# DDR3-RAM.net
KiCad netlist of a schematic drawn in Altium Designer
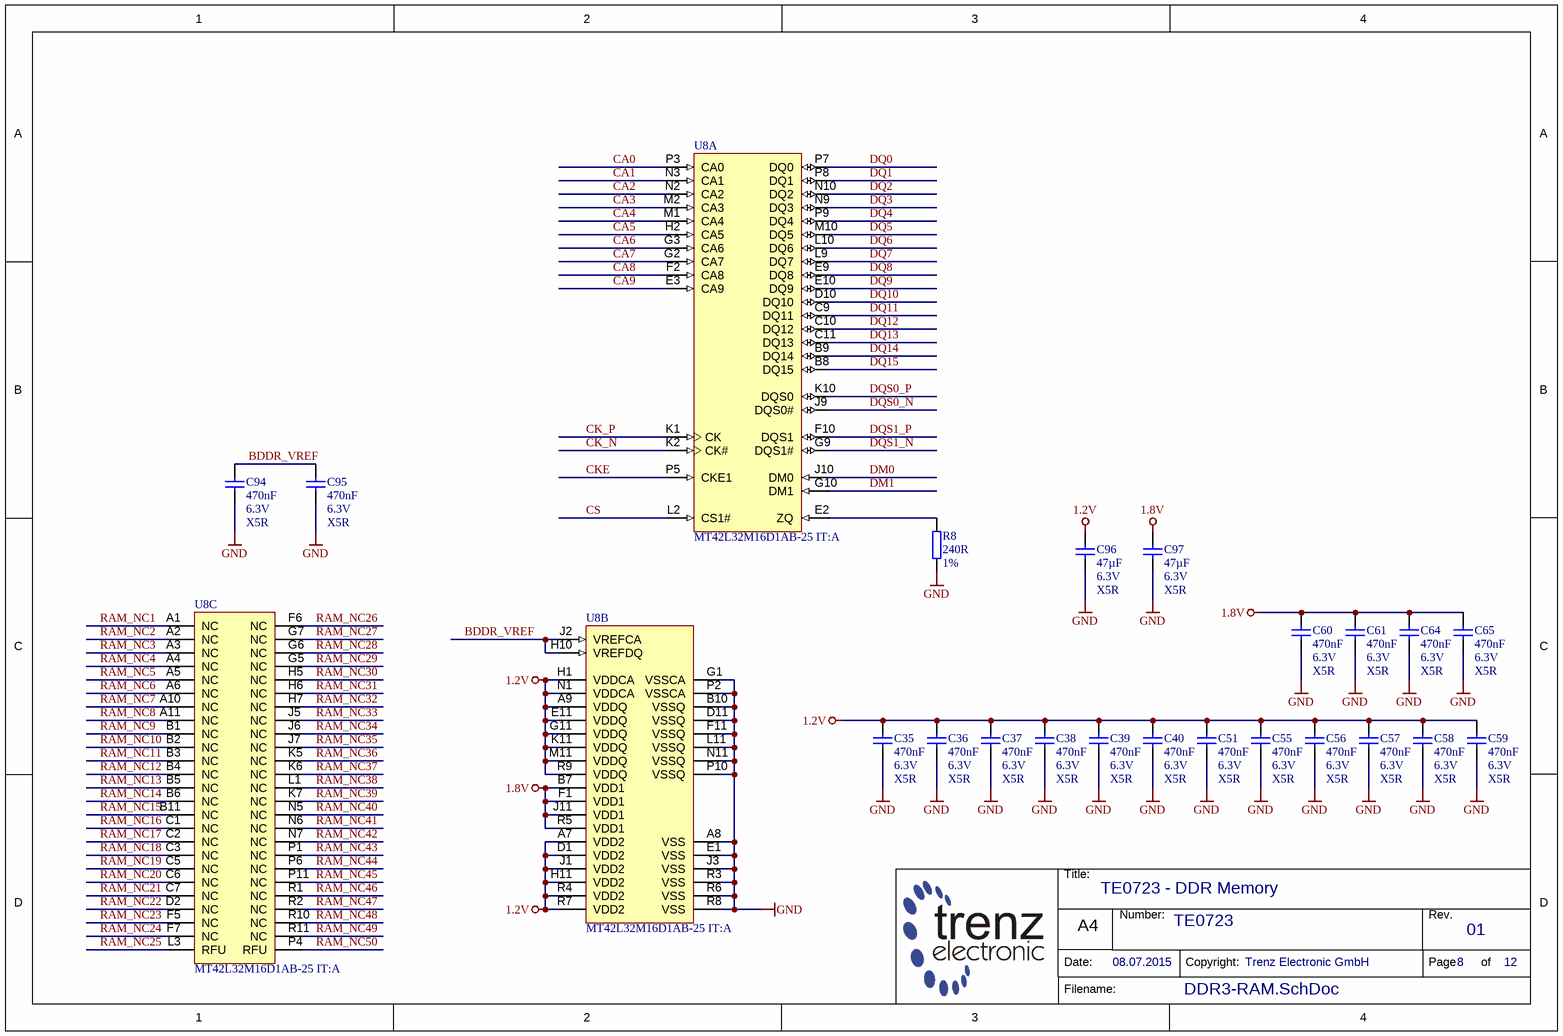
[diagram p0: DDR3-RAM.SchDoc]

(export (version "E")
  (design (tool "Eeschema 10.0.6"))
  (components
    (comp (ref "C35")
      (value "470nF")
      (footprint "CAPC0603X33N")
      (description "KON 470nF X5R 6.3V SMD 20%")
      (fields
        (field (name "VOLTAGE") "6.3V")
        (field (name "TECHNOLOGY") "X5R")
        (field (name "TOLERANCE") "20%")
      )
      (libsource (lib "TE") (part "CAP-NP"))
    )
    (comp (ref "C36")
      (value "470nF")
      (footprint "CAPC0603X33N")
      (description "KON 470nF X5R 6.3V SMD 20%")
      (fields
        (field (name "VOLTAGE") "6.3V")
        (field (name "TECHNOLOGY") "X5R")
        (field (name "TOLERANCE") "20%")
      )
      (libsource (lib "TE") (part "CAP-NP"))
    )
    (comp (ref "C37")
      (value "470nF")
      (footprint "CAPC0603X33N")
      (description "KON 470nF X5R 6.3V SMD 20%")
      (fields
        (field (name "VOLTAGE") "6.3V")
        (field (name "TECHNOLOGY") "X5R")
        (field (name "TOLERANCE") "20%")
      )
      (libsource (lib "TE") (part "CAP-NP"))
    )
    (comp (ref "C38")
      (value "470nF")
      (footprint "CAPC0603X33N")
      (description "KON 470nF X5R 6.3V SMD 20%")
      (fields
        (field (name "VOLTAGE") "6.3V")
        (field (name "TECHNOLOGY") "X5R")
        (field (name "TOLERANCE") "20%")
      )
      (libsource (lib "TE") (part "CAP-NP"))
    )
    (comp (ref "C39")
      (value "470nF")
      (footprint "CAPC0603X33N")
      (description "KON 470nF X5R 6.3V SMD 20%")
      (fields
        (field (name "VOLTAGE") "6.3V")
        (field (name "TECHNOLOGY") "X5R")
        (field (name "TOLERANCE") "20%")
      )
      (libsource (lib "TE") (part "CAP-NP"))
    )
    (comp (ref "C40")
      (value "470nF")
      (footprint "CAPC0603X33N")
      (description "KON 470nF X5R 6.3V SMD 20%")
      (fields
        (field (name "VOLTAGE") "6.3V")
        (field (name "TECHNOLOGY") "X5R")
        (field (name "TOLERANCE") "20%")
      )
      (libsource (lib "TE") (part "CAP-NP"))
    )
    (comp (ref "C51")
      (value "470nF")
      (footprint "CAPC0603X33N")
      (description "KON 470nF X5R 6.3V SMD 20%")
      (fields
        (field (name "VOLTAGE") "6.3V")
        (field (name "TECHNOLOGY") "X5R")
        (field (name "TOLERANCE") "20%")
      )
      (libsource (lib "TE") (part "CAP-NP"))
    )
    (comp (ref "C55")
      (value "470nF")
      (footprint "CAPC0603X33N")
      (description "KON 470nF X5R 6.3V SMD 20%")
      (fields
        (field (name "VOLTAGE") "6.3V")
        (field (name "TECHNOLOGY") "X5R")
        (field (name "TOLERANCE") "20%")
      )
      (libsource (lib "TE") (part "CAP-NP"))
    )
    (comp (ref "C56")
      (value "470nF")
      (footprint "CAPC0603X33N")
      (description "KON 470nF X5R 6.3V SMD 20%")
      (fields
        (field (name "VOLTAGE") "6.3V")
        (field (name "TECHNOLOGY") "X5R")
        (field (name "TOLERANCE") "20%")
      )
      (libsource (lib "TE") (part "CAP-NP"))
    )
    (comp (ref "C57")
      (value "470nF")
      (footprint "CAPC0603X33N")
      (description "KON 470nF X5R 6.3V SMD 20%")
      (fields
        (field (name "VOLTAGE") "6.3V")
        (field (name "TECHNOLOGY") "X5R")
        (field (name "TOLERANCE") "20%")
      )
      (libsource (lib "TE") (part "CAP-NP"))
    )
    (comp (ref "C58")
      (value "470nF")
      (footprint "CAPC0603X33N")
      (description "KON 470nF X5R 6.3V SMD 20%")
      (fields
        (field (name "VOLTAGE") "6.3V")
        (field (name "TECHNOLOGY") "X5R")
        (field (name "TOLERANCE") "20%")
      )
      (libsource (lib "TE") (part "CAP-NP"))
    )
    (comp (ref "C59")
      (value "470nF")
      (footprint "CAPC0603X33N")
      (description "KON 470nF X5R 6.3V SMD 20%")
      (fields
        (field (name "VOLTAGE") "6.3V")
        (field (name "TECHNOLOGY") "X5R")
        (field (name "TOLERANCE") "20%")
      )
      (libsource (lib "TE") (part "CAP-NP"))
    )
    (comp (ref "C60")
      (value "470nF")
      (footprint "CAPC0603X33N")
      (description "KON 470nF X5R 6.3V SMD 20%")
      (fields
        (field (name "VOLTAGE") "6.3V")
        (field (name "TECHNOLOGY") "X5R")
        (field (name "TOLERANCE") "20%")
      )
      (libsource (lib "TE") (part "CAP-NP"))
    )
    (comp (ref "C61")
      (value "470nF")
      (footprint "CAPC0603X33N")
      (description "KON 470nF X5R 6.3V SMD 20%")
      (fields
        (field (name "VOLTAGE") "6.3V")
        (field (name "TECHNOLOGY") "X5R")
        (field (name "TOLERANCE") "20%")
      )
      (libsource (lib "TE") (part "CAP-NP"))
    )
    (comp (ref "C64")
      (value "470nF")
      (footprint "CAPC0603X33N")
      (description "KON 470nF X5R 6.3V SMD 20%")
      (fields
        (field (name "VOLTAGE") "6.3V")
        (field (name "TECHNOLOGY") "X5R")
        (field (name "TOLERANCE") "20%")
      )
      (libsource (lib "TE") (part "CAP-NP"))
    )
    (comp (ref "C65")
      (value "470nF")
      (footprint "CAPC0603X33N")
      (description "KON 470nF X5R 6.3V SMD 20%")
      (fields
        (field (name "VOLTAGE") "6.3V")
        (field (name "TECHNOLOGY") "X5R")
        (field (name "TOLERANCE") "20%")
      )
      (libsource (lib "TE") (part "CAP-NP"))
    )
    (comp (ref "C94")
      (value "470nF")
      (footprint "CAPC0603X33N")
      (description "KON 470nF X5R 6.3V SMD 20%")
      (fields
        (field (name "VOLTAGE") "6.3V")
        (field (name "TECHNOLOGY") "X5R")
        (field (name "TOLERANCE") "20%")
      )
      (libsource (lib "TE") (part "CAP-NP"))
    )
    (comp (ref "C95")
      (value "470nF")
      (footprint "CAPC0603X33N")
      (description "KON 470nF X5R 6.3V SMD 20%")
      (fields
        (field (name "VOLTAGE") "6.3V")
        (field (name "TECHNOLOGY") "X5R")
        (field (name "TOLERANCE") "20%")
      )
      (libsource (lib "TE") (part "CAP-NP"))
    )
    (comp (ref "C96")
      (value "47µF")
      (footprint "CAPC2012X135N")
      (description "KON 47µF 6,3V  X5R SMD 20%")
      (fields
        (field (name "VOLTAGE") "6.3V")
        (field (name "TECHNOLOGY") "X5R")
        (field (name "TOLERANCE") "20%")
      )
      (libsource (lib "TE") (part "CAP-NP"))
    )
    (comp (ref "C97")
      (value "47µF")
      (footprint "CAPC2012X135N")
      (description "KON 47µF 6,3V  X5R SMD 20%")
      (fields
        (field (name "VOLTAGE") "6.3V")
        (field (name "TECHNOLOGY") "X5R")
        (field (name "TOLERANCE") "20%")
      )
      (libsource (lib "TE") (part "CAP-NP"))
    )
    (comp (ref "R8")
      (value "240R")
      (footprint "RESC1005X40N")
      (description "WID SMD 240R 1% 0,063W")
      (fields (field (name "TOLERANCE") "1%"))
      (libsource (lib "TE") (part "RES"))
    )
    (comp (ref "U8")
      (value "MT42L32M16D1AB-25 IT:A")
      (footprint "BGA121C50P15X11_800X650X80B32N")
      (libsource (lib "TE") (part "MT42L32M16D1AB"))
    )
  )
  (nets
    (net (code "1") (name "/BDDR_VREF") (class "Default")
      (node (ref "C94") (pin "1") (pinfunction "1_1") (pintype "passive"))
      (node (ref "C95") (pin "1") (pinfunction "1_1") (pintype "passive"))
      (node (ref "U8") (pin "H10") (pinfunction "VREFDQ_H10") (pintype "input"))
      (node (ref "U8") (pin "J2") (pinfunction "VREFCA_J2") (pintype "input"))
    )
    (net (code "2") (name "/CA0") (class "Default")
      (node (ref "U8") (pin "P3") (pinfunction "CA0_P3") (pintype "input"))
    )
    (net (code "3") (name "/CA1") (class "Default")
      (node (ref "U8") (pin "N3") (pinfunction "CA1_N3") (pintype "input"))
    )
    (net (code "4") (name "/CA2") (class "Default")
      (node (ref "U8") (pin "N2") (pinfunction "CA2_N2") (pintype "input"))
    )
    (net (code "5") (name "/CA3") (class "Default")
      (node (ref "U8") (pin "M2") (pinfunction "CA3_M2") (pintype "input"))
    )
    (net (code "6") (name "/CA4") (class "Default")
      (node (ref "U8") (pin "M1") (pinfunction "CA4_M1") (pintype "input"))
    )
    (net (code "7") (name "/CA5") (class "Default")
      (node (ref "U8") (pin "H2") (pinfunction "CA5_H2") (pintype "input"))
    )
    (net (code "8") (name "/CA6") (class "Default")
      (node (ref "U8") (pin "G3") (pinfunction "CA6_G3") (pintype "input"))
    )
    (net (code "9") (name "/CA7") (class "Default")
      (node (ref "U8") (pin "G2") (pinfunction "CA7_G2") (pintype "input"))
    )
    (net (code "10") (name "/CA8") (class "Default")
      (node (ref "U8") (pin "F2") (pinfunction "CA8_F2") (pintype "input"))
    )
    (net (code "11") (name "/CA9") (class "Default")
      (node (ref "U8") (pin "E3") (pinfunction "CA9_E3") (pintype "input"))
    )
    (net (code "12") (name "/CKE") (class "Default")
      (node (ref "U8") (pin "P5") (pinfunction "CKE1_P5") (pintype "input"))
    )
    (net (code "13") (name "/CK_N") (class "Default")
      (node (ref "U8") (pin "K2") (pinfunction "CK#_K2") (pintype "input"))
    )
    (net (code "14") (name "/CK_P") (class "Default")
      (node (ref "U8") (pin "K1") (pinfunction "CK_K1") (pintype "input"))
    )
    (net (code "15") (name "/CS") (class "Default")
      (node (ref "U8") (pin "L2") (pinfunction "CS1#_L2") (pintype "input"))
    )
    (net (code "16") (name "/DM0") (class "Default")
      (node (ref "U8") (pin "J10") (pinfunction "DM0_J10") (pintype "input"))
    )
    (net (code "17") (name "/DM1") (class "Default")
      (node (ref "U8") (pin "G10") (pinfunction "DM1_G10") (pintype "input"))
    )
    (net (code "18") (name "/DQ0") (class "Default")
      (node (ref "U8") (pin "P7") (pinfunction "DQ0_P7") (pintype "bidirectional"))
    )
    (net (code "19") (name "/DQ1") (class "Default")
      (node (ref "U8") (pin "P8") (pinfunction "DQ1_P8") (pintype "bidirectional"))
    )
    (net (code "20") (name "/DQ2") (class "Default")
      (node (ref "U8") (pin "N10") (pinfunction "DQ2_N10") (pintype "bidirectional"))
    )
    (net (code "21") (name "/DQ3") (class "Default")
      (node (ref "U8") (pin "N9") (pinfunction "DQ3_N9") (pintype "bidirectional"))
    )
    (net (code "22") (name "/DQ4") (class "Default")
      (node (ref "U8") (pin "P9") (pinfunction "DQ4_P9") (pintype "bidirectional"))
    )
    (net (code "23") (name "/DQ5") (class "Default")
      (node (ref "U8") (pin "M10") (pinfunction "DQ5_M10") (pintype "bidirectional"))
    )
    (net (code "24") (name "/DQ6") (class "Default")
      (node (ref "U8") (pin "L10") (pinfunction "DQ6_L10") (pintype "bidirectional"))
    )
    (net (code "25") (name "/DQ7") (class "Default")
      (node (ref "U8") (pin "L9") (pinfunction "DQ7_L9") (pintype "bidirectional"))
    )
    (net (code "26") (name "/DQ8") (class "Default")
      (node (ref "U8") (pin "E9") (pinfunction "DQ8_E9") (pintype "bidirectional"))
    )
    (net (code "27") (name "/DQ9") (class "Default")
      (node (ref "U8") (pin "E10") (pinfunction "DQ9_E10") (pintype "bidirectional"))
    )
    (net (code "28") (name "/DQ10") (class "Default")
      (node (ref "U8") (pin "D10") (pinfunction "DQ10_D10") (pintype "bidirectional"))
    )
    (net (code "29") (name "/DQ11") (class "Default")
      (node (ref "U8") (pin "C9") (pinfunction "DQ11_C9") (pintype "bidirectional"))
    )
    (net (code "30") (name "/DQ12") (class "Default")
      (node (ref "U8") (pin "C10") (pinfunction "DQ12_C10") (pintype "bidirectional"))
    )
    (net (code "31") (name "/DQ13") (class "Default")
      (node (ref "U8") (pin "C11") (pinfunction "DQ13_C11") (pintype "bidirectional"))
    )
    (net (code "32") (name "/DQ14") (class "Default")
      (node (ref "U8") (pin "B9") (pinfunction "DQ14_B9") (pintype "bidirectional"))
    )
    (net (code "33") (name "/DQ15") (class "Default")
      (node (ref "U8") (pin "B8") (pinfunction "DQ15_B8") (pintype "bidirectional"))
    )
    (net (code "34") (name "/DQS0_N") (class "Default")
      (node (ref "U8") (pin "J9") (pinfunction "DQS0#_J9") (pintype "bidirectional"))
    )
    (net (code "35") (name "/DQS0_P") (class "Default")
      (node (ref "U8") (pin "K10") (pinfunction "DQS0_K10") (pintype "bidirectional"))
    )
    (net (code "36") (name "/DQS1_N") (class "Default")
      (node (ref "U8") (pin "G9") (pinfunction "DQS1#_G9") (pintype "bidirectional"))
    )
    (net (code "37") (name "/DQS1_P") (class "Default")
      (node (ref "U8") (pin "F10") (pinfunction "DQS1_F10") (pintype "bidirectional"))
    )
    (net (code "38") (name "/RAM_NC1") (class "Default")
      (node (ref "U8") (pin "A1") (pinfunction "NC_A1") (pintype "passive"))
    )
    (net (code "39") (name "/RAM_NC2") (class "Default")
      (node (ref "U8") (pin "A2") (pinfunction "NC_A2") (pintype "passive"))
    )
    (net (code "40") (name "/RAM_NC3") (class "Default")
      (node (ref "U8") (pin "A3") (pinfunction "NC_A3") (pintype "passive"))
    )
    (net (code "41") (name "/RAM_NC4") (class "Default")
      (node (ref "U8") (pin "A4") (pinfunction "NC_A4") (pintype "passive"))
    )
    (net (code "42") (name "/RAM_NC5") (class "Default")
      (node (ref "U8") (pin "A5") (pinfunction "NC_A5") (pintype "passive"))
    )
    (net (code "43") (name "/RAM_NC6") (class "Default")
      (node (ref "U8") (pin "A6") (pinfunction "NC_A6") (pintype "passive"))
    )
    (net (code "44") (name "/RAM_NC7") (class "Default")
      (node (ref "U8") (pin "A10") (pinfunction "NC_A10") (pintype "passive"))
    )
    (net (code "45") (name "/RAM_NC8") (class "Default")
      (node (ref "U8") (pin "A11") (pinfunction "NC_A11") (pintype "passive"))
    )
    (net (code "46") (name "/RAM_NC9") (class "Default")
      (node (ref "U8") (pin "B1") (pinfunction "NC_B1") (pintype "passive"))
    )
    (net (code "47") (name "/RAM_NC10") (class "Default")
      (node (ref "U8") (pin "B2") (pinfunction "NC_B2") (pintype "passive"))
    )
    (net (code "48") (name "/RAM_NC11") (class "Default")
      (node (ref "U8") (pin "B3") (pinfunction "NC_B3") (pintype "passive"))
    )
    (net (code "49") (name "/RAM_NC12") (class "Default")
      (node (ref "U8") (pin "B4") (pinfunction "NC_B4") (pintype "passive"))
    )
    (net (code "50") (name "/RAM_NC13") (class "Default")
      (node (ref "U8") (pin "B5") (pinfunction "NC_B5") (pintype "passive"))
    )
    (net (code "51") (name "/RAM_NC14") (class "Default")
      (node (ref "U8") (pin "B6") (pinfunction "NC_B6") (pintype "passive"))
    )
    (net (code "52") (name "/RAM_NC15") (class "Default")
      (node (ref "U8") (pin "B11") (pinfunction "NC_B11") (pintype "passive"))
    )
    (net (code "53") (name "/RAM_NC16") (class "Default")
      (node (ref "U8") (pin "C1") (pinfunction "NC_C1") (pintype "passive"))
    )
    (net (code "54") (name "/RAM_NC17") (class "Default")
      (node (ref "U8") (pin "C2") (pinfunction "NC_C2") (pintype "passive"))
    )
    (net (code "55") (name "/RAM_NC18") (class "Default")
      (node (ref "U8") (pin "C3") (pinfunction "NC_C3") (pintype "passive"))
    )
    (net (code "56") (name "/RAM_NC19") (class "Default")
      (node (ref "U8") (pin "C5") (pinfunction "NC_C5") (pintype "passive"))
    )
    (net (code "57") (name "/RAM_NC20") (class "Default")
      (node (ref "U8") (pin "C6") (pinfunction "NC_C6") (pintype "passive"))
    )
    (net (code "58") (name "/RAM_NC21") (class "Default")
      (node (ref "U8") (pin "C7") (pinfunction "NC_C7") (pintype "passive"))
    )
    (net (code "59") (name "/RAM_NC22") (class "Default")
      (node (ref "U8") (pin "D2") (pinfunction "NC_D2") (pintype "passive"))
    )
    (net (code "60") (name "/RAM_NC23") (class "Default")
      (node (ref "U8") (pin "F5") (pinfunction "NC_F5") (pintype "passive"))
    )
    (net (code "61") (name "/RAM_NC24") (class "Default")
      (node (ref "U8") (pin "F7") (pinfunction "NC_F7") (pintype "passive"))
    )
    (net (code "62") (name "/RAM_NC25") (class "Default")
      (node (ref "U8") (pin "L3") (pinfunction "RFU_L3") (pintype "passive"))
    )
    (net (code "63") (name "/RAM_NC26") (class "Default")
      (node (ref "U8") (pin "F6") (pinfunction "NC_F6") (pintype "passive"))
    )
    (net (code "64") (name "/RAM_NC27") (class "Default")
      (node (ref "U8") (pin "G7") (pinfunction "NC_G7") (pintype "passive"))
    )
    (net (code "65") (name "/RAM_NC28") (class "Default")
      (node (ref "U8") (pin "G6") (pinfunction "NC_G6") (pintype "passive"))
    )
    (net (code "66") (name "/RAM_NC29") (class "Default")
      (node (ref "U8") (pin "G5") (pinfunction "NC_G5") (pintype "passive"))
    )
    (net (code "67") (name "/RAM_NC30") (class "Default")
      (node (ref "U8") (pin "H5") (pinfunction "NC_H5") (pintype "passive"))
    )
    (net (code "68") (name "/RAM_NC31") (class "Default")
      (node (ref "U8") (pin "H6") (pinfunction "NC_H6") (pintype "passive"))
    )
    (net (code "69") (name "/RAM_NC32") (class "Default")
      (node (ref "U8") (pin "H7") (pinfunction "NC_H7") (pintype "passive"))
    )
    (net (code "70") (name "/RAM_NC33") (class "Default")
      (node (ref "U8") (pin "J5") (pinfunction "NC_J5") (pintype "passive"))
    )
    (net (code "71") (name "/RAM_NC34") (class "Default")
      (node (ref "U8") (pin "J6") (pinfunction "NC_J6") (pintype "passive"))
    )
    (net (code "72") (name "/RAM_NC35") (class "Default")
      (node (ref "U8") (pin "J7") (pinfunction "NC_J7") (pintype "passive"))
    )
    (net (code "73") (name "/RAM_NC36") (class "Default")
      (node (ref "U8") (pin "K5") (pinfunction "NC_K5") (pintype "passive"))
    )
    (net (code "74") (name "/RAM_NC37") (class "Default")
      (node (ref "U8") (pin "K6") (pinfunction "NC_K6") (pintype "passive"))
    )
    (net (code "75") (name "/RAM_NC38") (class "Default")
      (node (ref "U8") (pin "L1") (pinfunction "NC_L1") (pintype "passive"))
    )
    (net (code "76") (name "/RAM_NC39") (class "Default")
      (node (ref "U8") (pin "K7") (pinfunction "NC_K7") (pintype "passive"))
    )
    (net (code "77") (name "/RAM_NC40") (class "Default")
      (node (ref "U8") (pin "N5") (pinfunction "NC_N5") (pintype "passive"))
    )
    (net (code "78") (name "/RAM_NC41") (class "Default")
      (node (ref "U8") (pin "N6") (pinfunction "NC_N6") (pintype "passive"))
    )
    (net (code "79") (name "/RAM_NC42") (class "Default")
      (node (ref "U8") (pin "N7") (pinfunction "NC_N7") (pintype "passive"))
    )
    (net (code "80") (name "/RAM_NC43") (class "Default")
      (node (ref "U8") (pin "P1") (pinfunction "NC_P1") (pintype "passive"))
    )
    (net (code "81") (name "/RAM_NC44") (class "Default")
      (node (ref "U8") (pin "P6") (pinfunction "NC_P6") (pintype "passive"))
    )
    (net (code "82") (name "/RAM_NC45") (class "Default")
      (node (ref "U8") (pin "P11") (pinfunction "NC_P11") (pintype "passive"))
    )
    (net (code "83") (name "/RAM_NC46") (class "Default")
      (node (ref "U8") (pin "R1") (pinfunction "NC_R1") (pintype "passive"))
    )
    (net (code "84") (name "/RAM_NC47") (class "Default")
      (node (ref "U8") (pin "R2") (pinfunction "NC_R2") (pintype "passive"))
    )
    (net (code "85") (name "/RAM_NC48") (class "Default")
      (node (ref "U8") (pin "R10") (pinfunction "NC_R10") (pintype "passive"))
    )
    (net (code "86") (name "/RAM_NC49") (class "Default")
      (node (ref "U8") (pin "R11") (pinfunction "NC_R11") (pintype "passive"))
    )
    (net (code "87") (name "/RAM_NC50") (class "Default")
      (node (ref "U8") (pin "P4") (pinfunction "RFU_P4") (pintype "passive"))
    )
    (net (code "88") (name "1.2V") (class "Default")
      (node (ref "C35") (pin "1") (pinfunction "1_1") (pintype "passive"))
      (node (ref "C36") (pin "1") (pinfunction "1_1") (pintype "passive"))
      (node (ref "C37") (pin "1") (pinfunction "1_1") (pintype "passive"))
      (node (ref "C38") (pin "1") (pinfunction "1_1") (pintype "passive"))
      (node (ref "C39") (pin "1") (pinfunction "1_1") (pintype "passive"))
      (node (ref "C40") (pin "1") (pinfunction "1_1") (pintype "passive"))
      (node (ref "C51") (pin "1") (pinfunction "1_1") (pintype "passive"))
      (node (ref "C55") (pin "1") (pinfunction "1_1") (pintype "passive"))
      (node (ref "C56") (pin "1") (pinfunction "1_1") (pintype "passive"))
      (node (ref "C57") (pin "1") (pinfunction "1_1") (pintype "passive"))
      (node (ref "C58") (pin "1") (pinfunction "1_1") (pintype "passive"))
      (node (ref "C59") (pin "1") (pinfunction "1_1") (pintype "passive"))
      (node (ref "C96") (pin "1") (pinfunction "1_1") (pintype "passive"))
      (node (ref "U8") (pin "A7") (pinfunction "VDD2_A7") (pintype "power_in"))
      (node (ref "U8") (pin "A9") (pinfunction "VDDQ_A9") (pintype "power_in"))
      (node (ref "U8") (pin "D1") (pinfunction "VDD2_D1") (pintype "power_in"))
      (node (ref "U8") (pin "E11") (pinfunction "VDDQ_E11") (pintype "power_in"))
      (node (ref "U8") (pin "G11") (pinfunction "VDDQ_G11") (pintype "power_in"))
      (node (ref "U8") (pin "H1") (pinfunction "VDDCA_H1") (pintype "power_in"))
      (node (ref "U8") (pin "H11") (pinfunction "VDD2_H11") (pintype "power_in"))
      (node (ref "U8") (pin "J1") (pinfunction "VDD2_J1") (pintype "power_in"))
      (node (ref "U8") (pin "K11") (pinfunction "VDDQ_K11") (pintype "power_in"))
      (node (ref "U8") (pin "M11") (pinfunction "VDDQ_M11") (pintype "power_in"))
      (node (ref "U8") (pin "N1") (pinfunction "VDDCA_N1") (pintype "power_in"))
      (node (ref "U8") (pin "R4") (pinfunction "VDD2_R4") (pintype "power_in"))
      (node (ref "U8") (pin "R7") (pinfunction "VDD2_R7") (pintype "power_in"))
      (node (ref "U8") (pin "R9") (pinfunction "VDDQ_R9") (pintype "power_in"))
    )
    (net (code "89") (name "1.8V") (class "Default")
      (node (ref "C60") (pin "1") (pinfunction "1_1") (pintype "passive"))
      (node (ref "C61") (pin "1") (pinfunction "1_1") (pintype "passive"))
      (node (ref "C64") (pin "1") (pinfunction "1_1") (pintype "passive"))
      (node (ref "C65") (pin "1") (pinfunction "1_1") (pintype "passive"))
      (node (ref "C97") (pin "1") (pinfunction "1_1") (pintype "passive"))
      (node (ref "U8") (pin "B7") (pinfunction "VDD1_B7") (pintype "power_in"))
      (node (ref "U8") (pin "F1") (pinfunction "VDD1_F1") (pintype "power_in"))
      (node (ref "U8") (pin "J11") (pinfunction "VDD1_J11") (pintype "power_in"))
      (node (ref "U8") (pin "R5") (pinfunction "VDD1_R5") (pintype "power_in"))
    )
    (net (code "90") (name "GND") (class "Default")
      (node (ref "C35") (pin "2") (pinfunction "2_2") (pintype "passive"))
      (node (ref "C36") (pin "2") (pinfunction "2_2") (pintype "passive"))
      (node (ref "C37") (pin "2") (pinfunction "2_2") (pintype "passive"))
      (node (ref "C38") (pin "2") (pinfunction "2_2") (pintype "passive"))
      (node (ref "C39") (pin "2") (pinfunction "2_2") (pintype "passive"))
      (node (ref "C40") (pin "2") (pinfunction "2_2") (pintype "passive"))
      (node (ref "C51") (pin "2") (pinfunction "2_2") (pintype "passive"))
      (node (ref "C55") (pin "2") (pinfunction "2_2") (pintype "passive"))
      (node (ref "C56") (pin "2") (pinfunction "2_2") (pintype "passive"))
      (node (ref "C57") (pin "2") (pinfunction "2_2") (pintype "passive"))
      (node (ref "C58") (pin "2") (pinfunction "2_2") (pintype "passive"))
      (node (ref "C59") (pin "2") (pinfunction "2_2") (pintype "passive"))
      (node (ref "C60") (pin "2") (pinfunction "2_2") (pintype "passive"))
      (node (ref "C61") (pin "2") (pinfunction "2_2") (pintype "passive"))
      (node (ref "C64") (pin "2") (pinfunction "2_2") (pintype "passive"))
      (node (ref "C65") (pin "2") (pinfunction "2_2") (pintype "passive"))
      (node (ref "C94") (pin "2") (pinfunction "2_2") (pintype "passive"))
      (node (ref "C95") (pin "2") (pinfunction "2_2") (pintype "passive"))
      (node (ref "C96") (pin "2") (pinfunction "2_2") (pintype "passive"))
      (node (ref "C97") (pin "2") (pinfunction "2_2") (pintype "passive"))
      (node (ref "R8") (pin "2") (pinfunction "2_2") (pintype "passive"))
      (node (ref "U8") (pin "A8") (pinfunction "VSS_A8") (pintype "power_in"))
      (node (ref "U8") (pin "B10") (pinfunction "VSSQ_B10") (pintype "power_in"))
      (node (ref "U8") (pin "D11") (pinfunction "VSSQ_D11") (pintype "power_in"))
      (node (ref "U8") (pin "E1") (pinfunction "VSS_E1") (pintype "power_in"))
      (node (ref "U8") (pin "F11") (pinfunction "VSSQ_F11") (pintype "power_in"))
      (node (ref "U8") (pin "G1") (pinfunction "VSSCA_G1") (pintype "power_in"))
      (node (ref "U8") (pin "J3") (pinfunction "VSS_J3") (pintype "power_in"))
      (node (ref "U8") (pin "L11") (pinfunction "VSSQ_L11") (pintype "power_in"))
      (node (ref "U8") (pin "N11") (pinfunction "VSSQ_N11") (pintype "power_in"))
      (node (ref "U8") (pin "P10") (pinfunction "VSSQ_P10") (pintype "power_in"))
      (node (ref "U8") (pin "P2") (pinfunction "VSSCA_P2") (pintype "power_in"))
      (node (ref "U8") (pin "R3") (pinfunction "VSS_R3") (pintype "power_in"))
      (node (ref "U8") (pin "R6") (pinfunction "VSS_R6") (pintype "power_in"))
      (node (ref "U8") (pin "R8") (pinfunction "VSS_R8") (pintype "power_in"))
    )
    (net (code "91") (name "Net-(U8A-ZQ)") (class "Default")
      (node (ref "R8") (pin "1") (pinfunction "1_1") (pintype "passive"))
      (node (ref "U8") (pin "E2") (pinfunction "ZQ_E2") (pintype "input"))
    )
  )
)
